# audio_filter.net
KiCad netlist of a schematic drawn in Altium Designer
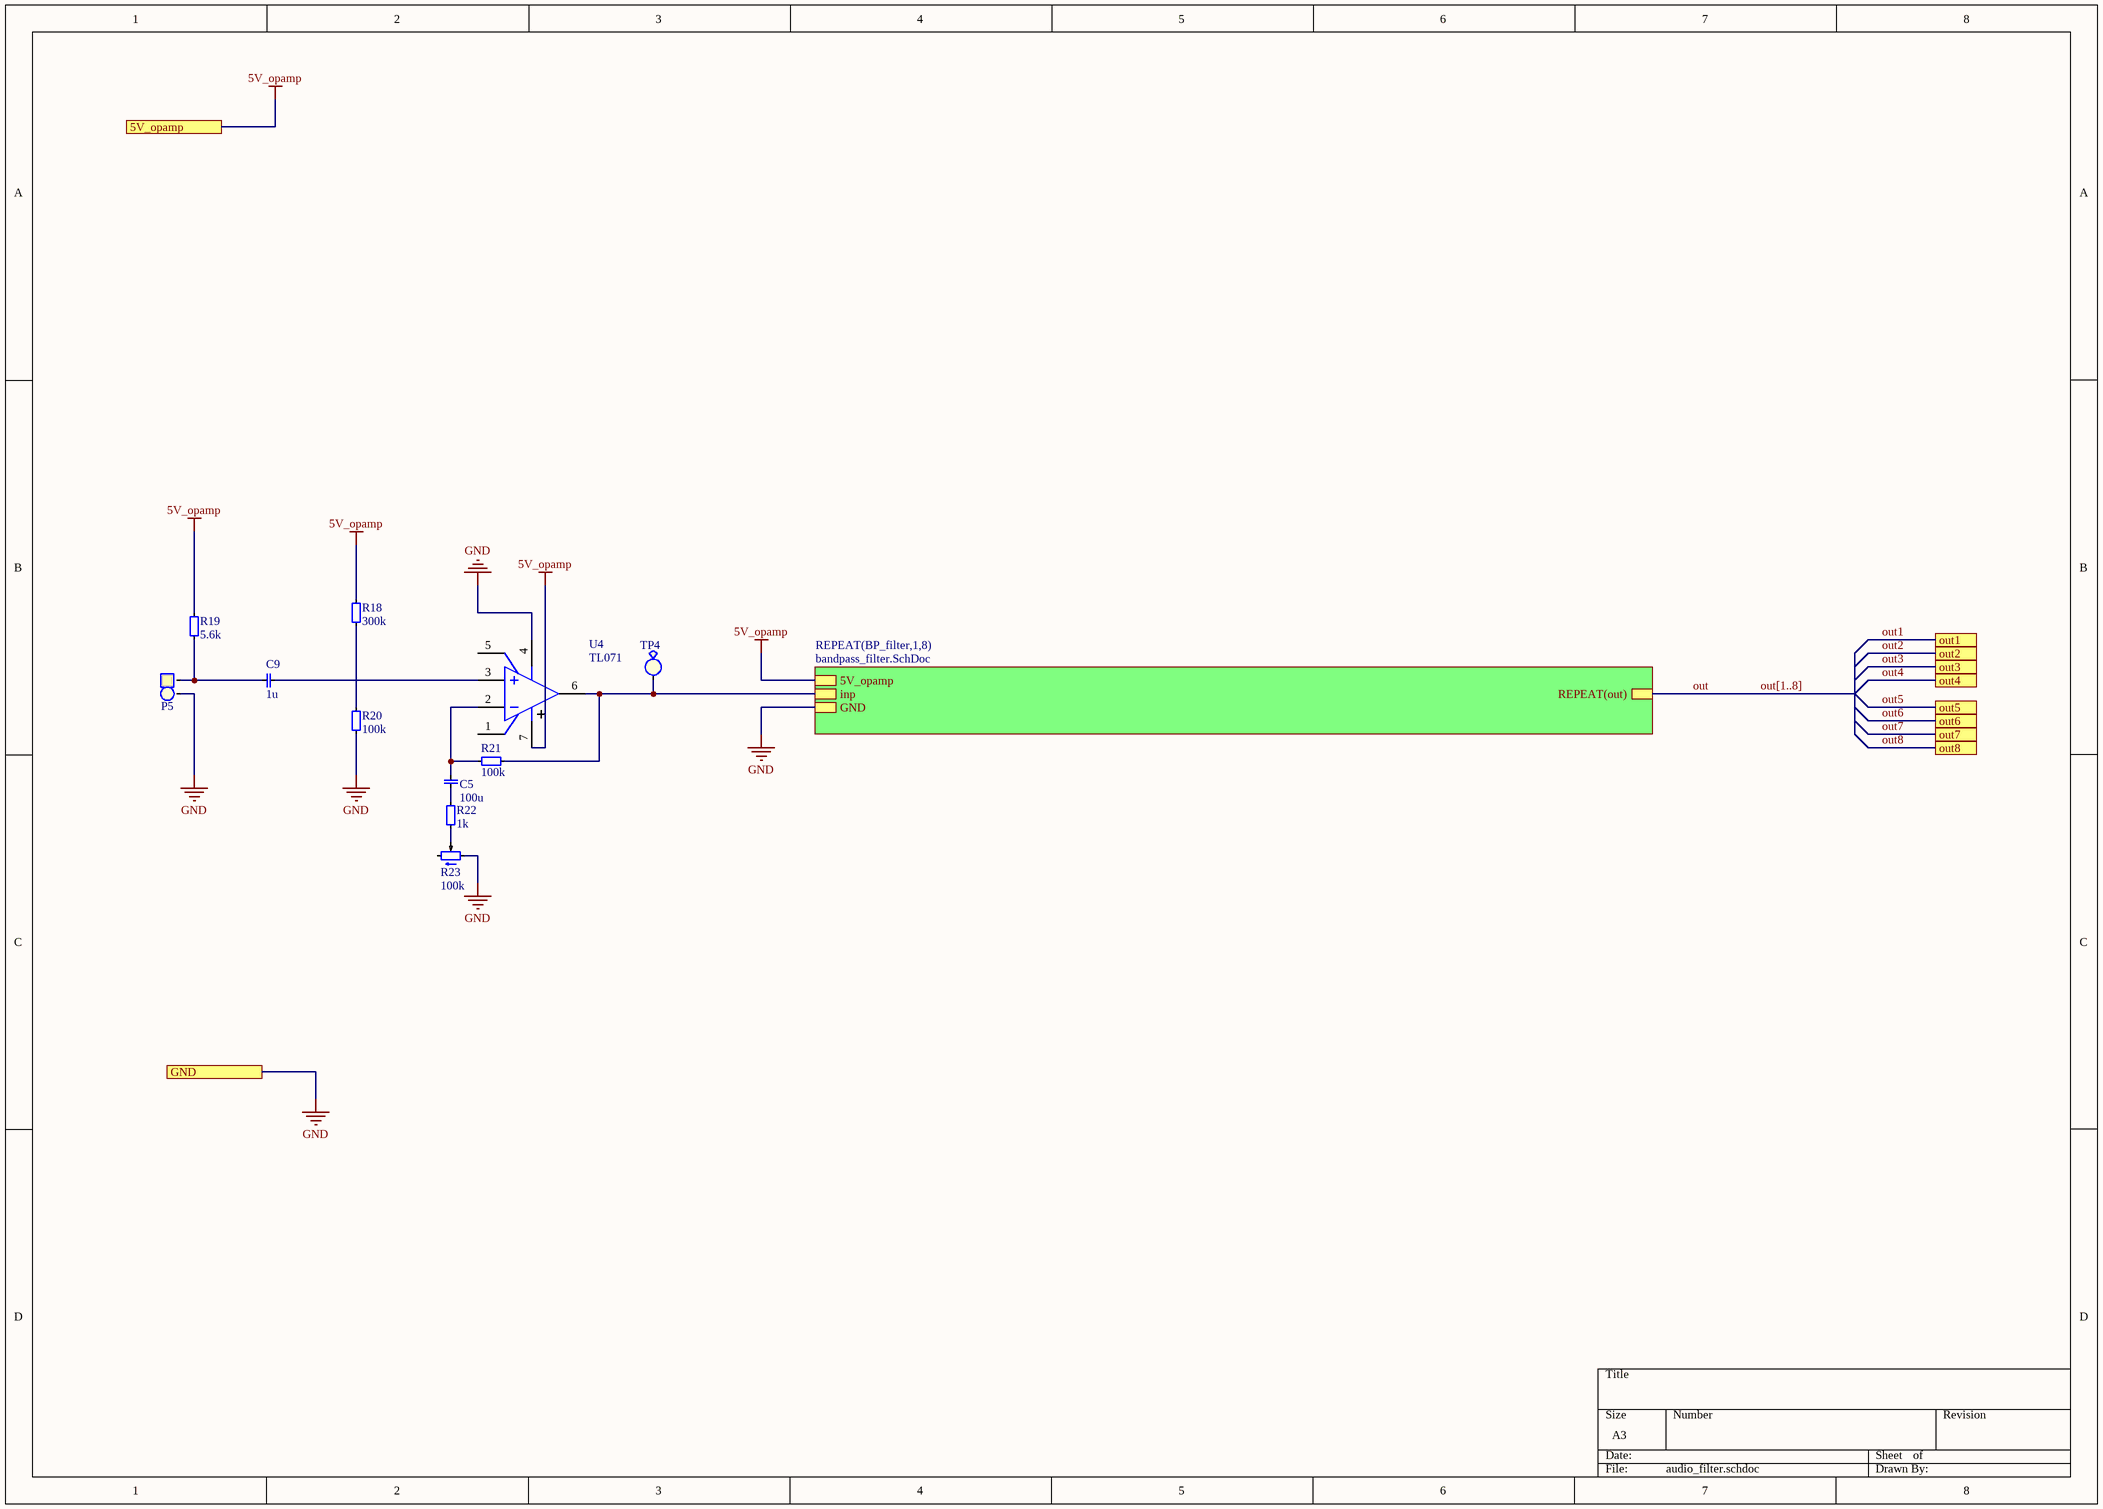
[diagram p0: audio_filter.schdoc]

(export (version "E")
  (design (tool "Eeschema 10.0.6"))
  (components
    (comp (ref "C5")
      (value "100u")
      (footprint "1206, capasitor")
      (fields (field (name "Comment") "1206, capacitor"))
      (libsource (lib "jclib") (part "1206, capacitor"))
    )
    (comp (ref "C9")
      (value "1u")
      (footprint "1206, capasitor")
      (fields (field (name "Comment") "1206, capacitor"))
      (libsource (lib "jclib") (part "1206, capacitor"))
    )
    (comp (ref "P5")
      (value "1x2 Pin Header")
      (footprint "padtwo_L")
      (description "2.54 mm, TH")
      (libsource (lib "jclib") (part "1x2 Pin Header"))
    )
    (comp (ref "R18")
      (value "300k")
      (footprint "1206")
      (description "Resistor")
      (fields (field (name "Comment") "1206, resistor"))
      (libsource (lib "jclib") (part "1206, resistor"))
    )
    (comp (ref "R19")
      (value "5.6k")
      (footprint "1206")
      (description "Resistor")
      (fields (field (name "Comment") "1206, resistor"))
      (libsource (lib "jclib") (part "1206, resistor"))
    )
    (comp (ref "R20")
      (value "100k")
      (footprint "1206")
      (description "Resistor")
      (fields (field (name "Comment") "1206, resistor"))
      (libsource (lib "jclib") (part "1206, resistor"))
    )
    (comp (ref "R21")
      (value "100k")
      (footprint "1206")
      (description "Resistor")
      (fields (field (name "Comment") "1206, resistor"))
      (libsource (lib "jclib") (part "1206, resistor"))
    )
    (comp (ref "R22")
      (value "1k")
      (footprint "1206")
      (description "Resistor")
      (fields (field (name "Comment") "1206, resistor"))
      (libsource (lib "jclib") (part "1206, resistor"))
    )
    (comp (ref "R23")
      (value "100k")
      (footprint "POT_TH1")
      (fields (field (name "Comment") "Pot"))
      (libsource (lib "jclib") (part "Pot"))
    )
    (comp (ref "TP4")
      (value "Test Point")
      (footprint "testPoint")
      (libsource (lib "jclib") (part "Test Point"))
    )
    (comp (ref "U4") (value "TL071") (footprint "SOIC8") (libsource (lib "jclib") (part "TL071")))
  )
  (nets
    (net (code "1") (name "/inp") (class "Default")
      (node (ref "R21") (pin "1") (pinfunction "1_1") (pintype "passive"))
      (node (ref "TP4") (pin "0") (pinfunction "0_0") (pintype "passive"))
      (node (ref "U4") (pin "6") (pinfunction "OUT_6") (pintype "passive"))
    )
    (net (code "12") (name "5V_opamp") (class "Default")
      (node (ref "R18") (pin "0") (pinfunction "0_0") (pintype "passive"))
      (node (ref "R19") (pin "0") (pinfunction "0_0") (pintype "passive"))
      (node (ref "U4") (pin "7") (pinfunction "V+_7") (pintype "passive"))
    )
    (net (code "13") (name "GND") (class "Default")
      (node (ref "P5") (pin "2") (pinfunction "2_2") (pintype "passive"))
      (node (ref "R20") (pin "1") (pinfunction "1_1") (pintype "passive"))
      (node (ref "R23") (pin "1") (pinfunction "1_1") (pintype "passive"))
      (node (ref "U4") (pin "4") (pinfunction "V-_4") (pintype "passive"))
    )
    (net (code "14") (name "Net-(C5-Pad1)") (class "Default")
      (node (ref "C5") (pin "1") (pinfunction "1_1") (pintype "passive"))
      (node (ref "R22") (pin "0") (pinfunction "0_0") (pintype "passive"))
    )
    (net (code "15") (name "Net-(C9-Pad1)") (class "Default")
      (node (ref "C9") (pin "1") (pinfunction "1_1") (pintype "passive"))
      (node (ref "P5") (pin "1") (pinfunction "1_1") (pintype "passive"))
      (node (ref "R19") (pin "1") (pinfunction "1_1") (pintype "passive"))
    )
    (net (code "16") (name "Net-(R18-Pad1)") (class "Default")
      (node (ref "R18") (pin "1") (pinfunction "1_1") (pintype "passive"))
      (node (ref "R20") (pin "0") (pinfunction "0_0") (pintype "passive"))
    )
    (net (code "17") (name "Net-(R22-Pad1)") (class "Default")
      (node (ref "R22") (pin "1") (pinfunction "1_1") (pintype "passive"))
      (node (ref "R23") (pin "2") (pinfunction "2_2") (pintype "passive"))
    )
    (net (code "18") (name "Net-(U4-IN+)") (class "Default")
      (node (ref "C9") (pin "0") (pinfunction "0_0") (pintype "passive"))
      (node (ref "U4") (pin "3") (pinfunction "IN+_3") (pintype "passive"))
    )
    (net (code "19") (name "Net-(U4-IN-)") (class "Default")
      (node (ref "C5") (pin "0") (pinfunction "0_0") (pintype "passive"))
      (node (ref "R21") (pin "0") (pinfunction "0_0") (pintype "passive"))
      (node (ref "U4") (pin "2") (pinfunction "IN-_2") (pintype "passive"))
    )
    (net (code "20") (name "unconnected-(R23-Pad3)") (class "Default")
      (node (ref "R23") (pin "3") (pinfunction "3_3") (pintype "passive"))
    )
    (net (code "21") (name "unconnected-(U4-OS_TRIM-Pad1)") (class "Default")
      (node (ref "U4") (pin "1") (pinfunction "OS_TRIM_1") (pintype "passive"))
    )
    (net (code "22") (name "unconnected-(U4-OS_TRIM-Pad5)") (class "Default")
      (node (ref "U4") (pin "5") (pinfunction "OS_TRIM_5") (pintype "passive"))
    )
  )
)
